# design.net
KiCad netlist of a schematic drawn in EasyEDA
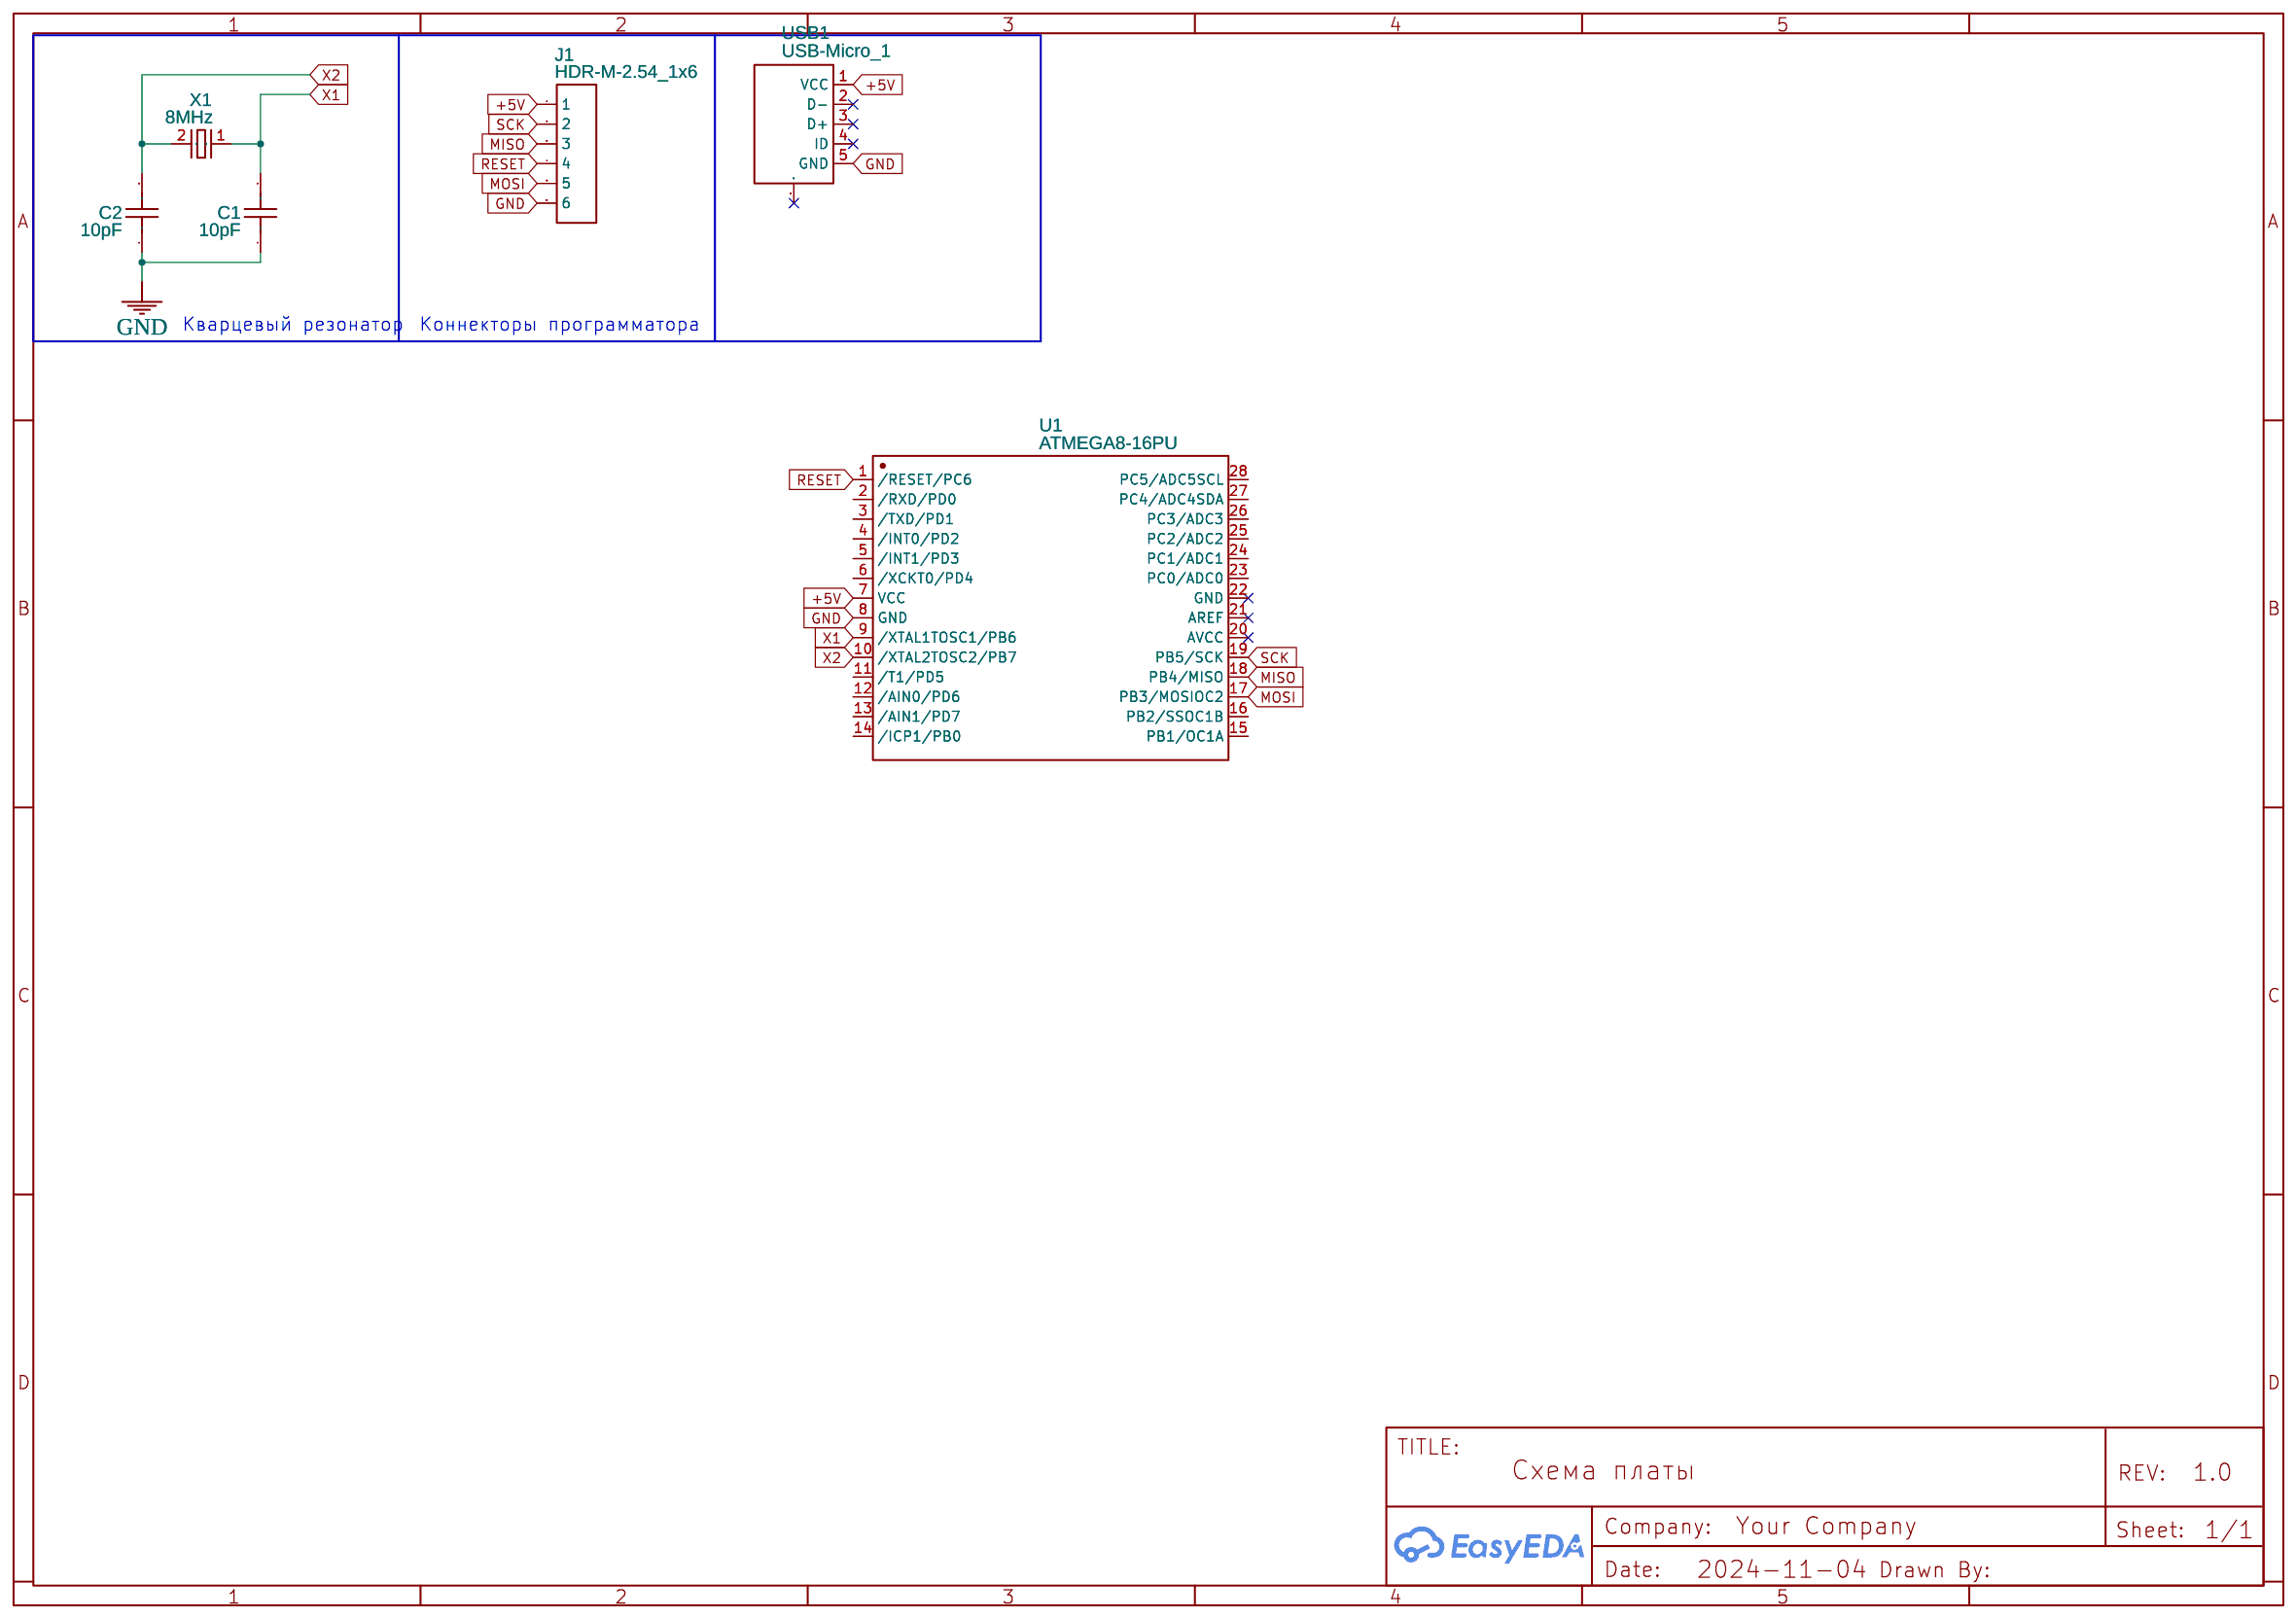
[diagram p0: schematic sheet]

(export (version "E")
  (design (tool "Eeschema 10.0.6"))
  (components
    (comp (ref "C1") (value "10pF") (libsource (lib "") (part "C_0603_US")))
    (comp (ref "C2") (value "10pF") (libsource (lib "") (part "C_0603_US")))
    (comp (ref "J1") (value "HDR-M-2.54_1x6") (libsource (lib "") (part "HDR-M-2.54_1x6")))
    (comp (ref "U1")
      (value "ATMEGA8-16PU")
      (fields (field (name "Manufacturer") "MICROCHIP(美国微芯)"))
      (libsource (lib "") (part "ATMEGA8-16PU"))
    )
    (comp (ref "USB1")
      (value "USB-Micro_1")
      (fields (field (name "Manufacturer") "ValuePro"))
      (libsource (lib "") (part "USB-Micro_1"))
    )
    (comp (ref "X1")
      (value "8MHz")
      (fields
        (field (name "Manufacturer Part") "NX3225GD-8MHZ-STD-CRA-3")
        (field (name "Manufacturer") "NDK")
      )
      (libsource (lib "") (part "NX3225GD-8MHZ-STD-CRA-3"))
    )
  )
  (nets
    (net (code "1") (name "+5V") (class "Default")
      (node (ref "J1") (pin "1") (pinfunction "1_1") (pintype "input"))
      (node (ref "U1") (pin "7") (pinfunction "VCC_7") (pintype "unspecified"))
      (node (ref "USB1") (pin "1") (pinfunction "VCC_1") (pintype "input"))
    )
    (net (code "2") (name "GND") (class "Default")
      (node (ref "C1") (pin "1") (pinfunction "1_1") (pintype "unspecified"))
      (node (ref "C2") (pin "1") (pinfunction "1_1") (pintype "unspecified"))
      (node (ref "J1") (pin "6") (pinfunction "6_6") (pintype "input"))
      (node (ref "U1") (pin "8") (pinfunction "GND_8") (pintype "unspecified"))
      (node (ref "USB1") (pin "5") (pinfunction "GND_5") (pintype "input"))
    )
    (net (code "3") (name "MISO") (class "Default")
      (node (ref "J1") (pin "3") (pinfunction "3_3") (pintype "input"))
      (node (ref "U1") (pin "18") (pinfunction "PB4/MISO_18") (pintype "unspecified"))
    )
    (net (code "4") (name "MOSI") (class "Default")
      (node (ref "J1") (pin "5") (pinfunction "5_5") (pintype "input"))
      (node (ref "U1") (pin "17") (pinfunction "PB3/MOSIOC2_17") (pintype "unspecified"))
    )
    (net (code "5") (name "RESET") (class "Default")
      (node (ref "J1") (pin "4") (pinfunction "4_4") (pintype "input"))
      (node (ref "U1") (pin "1") (pinfunction "/RESET/PC6_1") (pintype "unspecified"))
    )
    (net (code "6") (name "SCK") (class "Default")
      (node (ref "J1") (pin "2") (pinfunction "2_2") (pintype "input"))
      (node (ref "U1") (pin "19") (pinfunction "PB5/SCK_19") (pintype "unspecified"))
    )
    (net (code "7") (name "X1") (class "Default")
      (node (ref "C1") (pin "2") (pinfunction "2_2") (pintype "unspecified"))
      (node (ref "U1") (pin "9") (pinfunction "/XTAL1TOSC1/PB6_9") (pintype "unspecified"))
      (node (ref "X1") (pin "1") (pinfunction "1_1") (pintype "input"))
    )
    (net (code "8") (name "X2") (class "Default")
      (node (ref "C2") (pin "2") (pinfunction "2_2") (pintype "unspecified"))
      (node (ref "U1") (pin "10") (pinfunction "/XTAL2TOSC2/PB7_10") (pintype "unspecified"))
      (node (ref "X1") (pin "2") (pinfunction "GND_2") (pintype "input"))
    )
    (net (code "9") (name "unconnected-(U1-AREF-Pad21)") (class "Default")
      (node (ref "U1") (pin "21") (pinfunction "AREF_21") (pintype "unspecified+no_connect"))
    )
    (net (code "10") (name "unconnected-(U1-AVCC-Pad20)") (class "Default")
      (node (ref "U1") (pin "20") (pinfunction "AVCC_20") (pintype "unspecified+no_connect"))
    )
    (net (code "11") (name "unconnected-(U1-GND-Pad22)") (class "Default")
      (node (ref "U1") (pin "22") (pinfunction "GND_22") (pintype "unspecified+no_connect"))
    )
    (net (code "12") (name "unconnected-(U1-PB1{slash}OC1A-Pad15)") (class "Default")
      (node (ref "U1") (pin "15") (pinfunction "PB1/OC1A_15") (pintype "unspecified"))
    )
    (net (code "13") (name "unconnected-(U1-PB2{slash}SSOC1B-Pad16)") (class "Default")
      (node (ref "U1") (pin "16") (pinfunction "PB2/SSOC1B_16") (pintype "unspecified"))
    )
    (net (code "14") (name "unconnected-(U1-PC0{slash}ADC0-Pad23)") (class "Default")
      (node (ref "U1") (pin "23") (pinfunction "PC0/ADC0_23") (pintype "unspecified"))
    )
    (net (code "15") (name "unconnected-(U1-PC1{slash}ADC1-Pad24)") (class "Default")
      (node (ref "U1") (pin "24") (pinfunction "PC1/ADC1_24") (pintype "unspecified"))
    )
    (net (code "16") (name "unconnected-(U1-PC2{slash}ADC2-Pad25)") (class "Default")
      (node (ref "U1") (pin "25") (pinfunction "PC2/ADC2_25") (pintype "unspecified"))
    )
    (net (code "17") (name "unconnected-(U1-PC3{slash}ADC3-Pad26)") (class "Default")
      (node (ref "U1") (pin "26") (pinfunction "PC3/ADC3_26") (pintype "unspecified"))
    )
    (net (code "18") (name "unconnected-(U1-PC4{slash}ADC4SDA-Pad27)") (class "Default")
      (node (ref "U1") (pin "27") (pinfunction "PC4/ADC4SDA_27") (pintype "unspecified"))
    )
    (net (code "19") (name "unconnected-(U1-PC5{slash}ADC5SCL-Pad28)") (class "Default")
      (node (ref "U1") (pin "28") (pinfunction "PC5/ADC5SCL_28") (pintype "unspecified"))
    )
    (net (code "20") (name "unconnected-(U1-{slash}AIN0{slash}PD6-Pad12)") (class "Default")
      (node (ref "U1") (pin "12") (pinfunction "/AIN0/PD6_12") (pintype "unspecified"))
    )
    (net (code "21") (name "unconnected-(U1-{slash}AIN1{slash}PD7-Pad13)") (class "Default")
      (node (ref "U1") (pin "13") (pinfunction "/AIN1/PD7_13") (pintype "unspecified"))
    )
    (net (code "22") (name "unconnected-(U1-{slash}ICP1{slash}PB0-Pad14)") (class "Default")
      (node (ref "U1") (pin "14") (pinfunction "/ICP1/PB0_14") (pintype "unspecified"))
    )
    (net (code "23") (name "unconnected-(U1-{slash}INT0{slash}PD2-Pad4)") (class "Default")
      (node (ref "U1") (pin "4") (pinfunction "/INT0/PD2_4") (pintype "unspecified"))
    )
    (net (code "24") (name "unconnected-(U1-{slash}INT1{slash}PD3-Pad5)") (class "Default")
      (node (ref "U1") (pin "5") (pinfunction "/INT1/PD3_5") (pintype "unspecified"))
    )
    (net (code "25") (name "unconnected-(U1-{slash}RXD{slash}PD0-Pad2)") (class "Default")
      (node (ref "U1") (pin "2") (pinfunction "/RXD/PD0_2") (pintype "unspecified"))
    )
    (net (code "26") (name "unconnected-(U1-{slash}T1{slash}PD5-Pad11)") (class "Default")
      (node (ref "U1") (pin "11") (pinfunction "/T1/PD5_11") (pintype "unspecified"))
    )
    (net (code "27") (name "unconnected-(U1-{slash}TXD{slash}PD1-Pad3)") (class "Default")
      (node (ref "U1") (pin "3") (pinfunction "/TXD/PD1_3") (pintype "unspecified"))
    )
    (net (code "28") (name "unconnected-(U1-{slash}XCKT0{slash}PD4-Pad6)") (class "Default")
      (node (ref "U1") (pin "6") (pinfunction "/XCKT0/PD4_6") (pintype "unspecified"))
    )
    (net (code "29") (name "unconnected-(USB1-D+-Pad3)") (class "Default")
      (node (ref "USB1") (pin "3") (pinfunction "D+_3") (pintype "input+no_connect"))
    )
    (net (code "30") (name "unconnected-(USB1-D--Pad2)") (class "Default")
      (node (ref "USB1") (pin "2") (pinfunction "D-_2") (pintype "input+no_connect"))
    )
    (net (code "31") (name "unconnected-(USB1-ID-Pad4)") (class "Default")
      (node (ref "USB1") (pin "4") (pinfunction "ID_4") (pintype "input+no_connect"))
    )
    (net (code "32") (name "unconnected-(USB1-MTN-Pad0)") (class "Default")
      (node (ref "USB1") (pin "0") (pinfunction "MTN_0") (pintype "unspecified+no_connect"))
    )
  )
)
